# Sheet1.net
KiCad netlist of a schematic drawn in Altium Designer
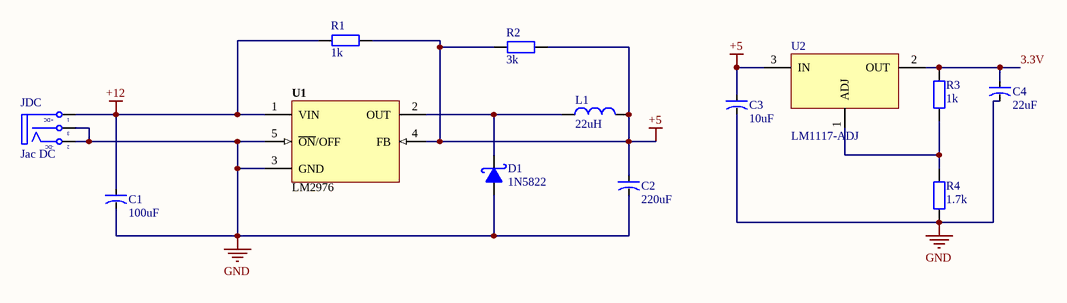
[diagram p0: Sheet1.SchDoc]

(export (version "E")
  (design (tool "Eeschema 10.0.6"))
  (components
    (comp (ref "C1")
      (value "100uF")
      (footprint "CAP-ALU-SMD-4.5x5x1.4")
      (description "Polarized Capacitor (Axial)")
      (fields (field (name "PUBLISHER") "Altium Limited"))
      (libsource (lib "My Library") (part "CAP-ALU-SMD"))
    )
    (comp (ref "C2")
      (value "220uF")
      (footprint "CAP-ALU-SMD-4.5x5x1.4")
      (description "Polarized Capacitor (Axial)")
      (fields (field (name "PUBLISHER") "Altium Limited"))
      (libsource (lib "My Library") (part "CAP-ALU-SMD"))
    )
    (comp (ref "C3")
      (value "10uF")
      (footprint "CAP-ALU-SMD-4.5x5x1.4")
      (description "Polarized Capacitor (Axial)")
      (fields (field (name "PUBLISHER") "Altium Limited"))
      (libsource (lib "My Library") (part "CAP-ALU-SMD"))
    )
    (comp (ref "C4")
      (value "22uF")
      (footprint "CA-ALU-2.54")
      (description "Capacitor (Semiconductor SIM Model)")
      (fields (field (name "PUBLISHER") "Altium Limited"))
      (libsource (lib "My Library") (part "CAP-ALU-DIP"))
    )
    (comp (ref "D1")
      (value "1N5822")
      (footprint "DIO-SMD-123")
      (description "Schottky Rectifiers")
      (libsource (lib "My Library") (part "1N5822"))
    )
    (comp (ref "JDC")
      (value "Jac DC")
      (footprint "DC-IN")
      (description "Jac DC input")
      (libsource (lib "My Library") (part "DCIN"))
    )
    (comp (ref "L1")
      (value "22uH")
      (footprint "L-SMD-M-12x10")
      (description "Inductor")
      (libsource (lib "My Library") (part "Inductor"))
    )
    (comp (ref "R1")
      (value "1k")
      (footprint "RES-SMD-0805")
      (description "Resistor SMD")
      (fields
        (field (name "MANUFACTURER") "Generic Components")
        (field (name "PUBLISHER") "Altium Hobart Technology Centre")
      )
      (libsource (lib "My Library") (part "Resistor - SMD"))
    )
    (comp (ref "R2")
      (value "3k")
      (footprint "RES-SMD-0805")
      (description "Resistor SMD")
      (fields
        (field (name "MANUFACTURER") "Generic Components")
        (field (name "PUBLISHER") "Altium Hobart Technology Centre")
      )
      (libsource (lib "My Library") (part "Resistor - SMD"))
    )
    (comp (ref "R3")
      (value "1k")
      (footprint "RES-SMD-0805")
      (description "Resistor SMD")
      (fields
        (field (name "MANUFACTURER") "Generic Components")
        (field (name "PUBLISHER") "Altium Hobart Technology Centre")
      )
      (libsource (lib "My Library") (part "Resistor - SMD"))
    )
    (comp (ref "R4")
      (value "1.7k")
      (footprint "RES-SMD-0805")
      (description "Resistor SMD")
      (fields
        (field (name "MANUFACTURER") "Generic Components")
        (field (name "PUBLISHER") "Altium Hobart Technology Centre")
      )
      (libsource (lib "My Library") (part "Resistor - SMD"))
    )
    (comp (ref "U1") (value "LM2976") (footprint "TO-263") (libsource (lib "My Library") (part "LM2596")))
    (comp (ref "U2")
      (value "LM1117-ADJ")
      (footprint "LM1117-SOP")
      (description "800mA Low-Dropout Linear Regulator")
      (fields (field (name "CREATOR") "Nguyen Ba Bien"))
      (libsource (lib "My Library") (part "LM1117-ADJ"))
    )
  )
  (nets
    (net (code "1") (name "+5") (class "Default")
      (node (ref "C2") (pin "1") (pinfunction "1_1") (pintype "passive"))
      (node (ref "C3") (pin "1") (pinfunction "1_1") (pintype "passive"))
      (node (ref "L1") (pin "2") (pinfunction "2_2") (pintype "passive"))
      (node (ref "R1") (pin "2") (pinfunction "2_2") (pintype "passive"))
      (node (ref "R2") (pin "1") (pinfunction "1_1") (pintype "passive"))
      (node (ref "R2") (pin "2") (pinfunction "2_2") (pintype "passive"))
      (node (ref "U1") (pin "4") (pinfunction "FB_4") (pintype "input"))
      (node (ref "U2") (pin "3") (pinfunction "IN_3") (pintype "passive"))
    )
    (net (code "2") (name "+12") (class "Default")
      (node (ref "C1") (pin "1") (pinfunction "1_1") (pintype "passive"))
      (node (ref "JDC") (pin "1") (pinfunction "T_1") (pintype "passive"))
      (node (ref "R1") (pin "1") (pinfunction "1_1") (pintype "passive"))
      (node (ref "U1") (pin "1") (pinfunction "VIN_1") (pintype "power_in"))
    )
    (net (code "3") (name "/3.3V") (class "Default")
      (node (ref "C4") (pin "1") (pinfunction "1_1") (pintype "passive"))
      (node (ref "R3") (pin "2") (pinfunction "2_2") (pintype "passive"))
      (node (ref "U2") (pin "2") (pinfunction "OUT_2") (pintype "passive"))
    )
    (net (code "4") (name "GND") (class "Default")
      (node (ref "C1") (pin "2") (pinfunction "2_2") (pintype "passive"))
      (node (ref "C2") (pin "2") (pinfunction "2_2") (pintype "passive"))
      (node (ref "C3") (pin "2") (pinfunction "2_2") (pintype "passive"))
      (node (ref "C4") (pin "2") (pinfunction "2_2") (pintype "passive"))
      (node (ref "D1") (pin "1") (pinfunction "A_1") (pintype "passive"))
      (node (ref "JDC") (pin "2") (pinfunction "TN_2") (pintype "passive"))
      (node (ref "JDC") (pin "3") (pinfunction "S_3") (pintype "power_in"))
      (node (ref "R4") (pin "2") (pinfunction "2_2") (pintype "passive"))
      (node (ref "U1") (pin "3") (pinfunction "GND_3") (pintype "power_in"))
      (node (ref "U1") (pin "5") (pinfunction "~{ON}/OFF_5") (pintype "input"))
    )
    (net (code "5") (name "Net-(D1-K)") (class "Default")
      (node (ref "D1") (pin "2") (pinfunction "K_2") (pintype "passive"))
      (node (ref "L1") (pin "1") (pinfunction "1_1") (pintype "passive"))
      (node (ref "U1") (pin "2") (pinfunction "OUT_2") (pintype "power_in"))
    )
    (net (code "6") (name "Net-(U2-ADJ)") (class "Default")
      (node (ref "R3") (pin "1") (pinfunction "1_1") (pintype "passive"))
      (node (ref "R4") (pin "1") (pinfunction "1_1") (pintype "passive"))
      (node (ref "U2") (pin "1") (pinfunction "ADJ_1") (pintype "passive"))
    )
  )
)
